# Simple_MacroPad_PCB.net
KiCad netlist of a schematic drawn in Altium Designer
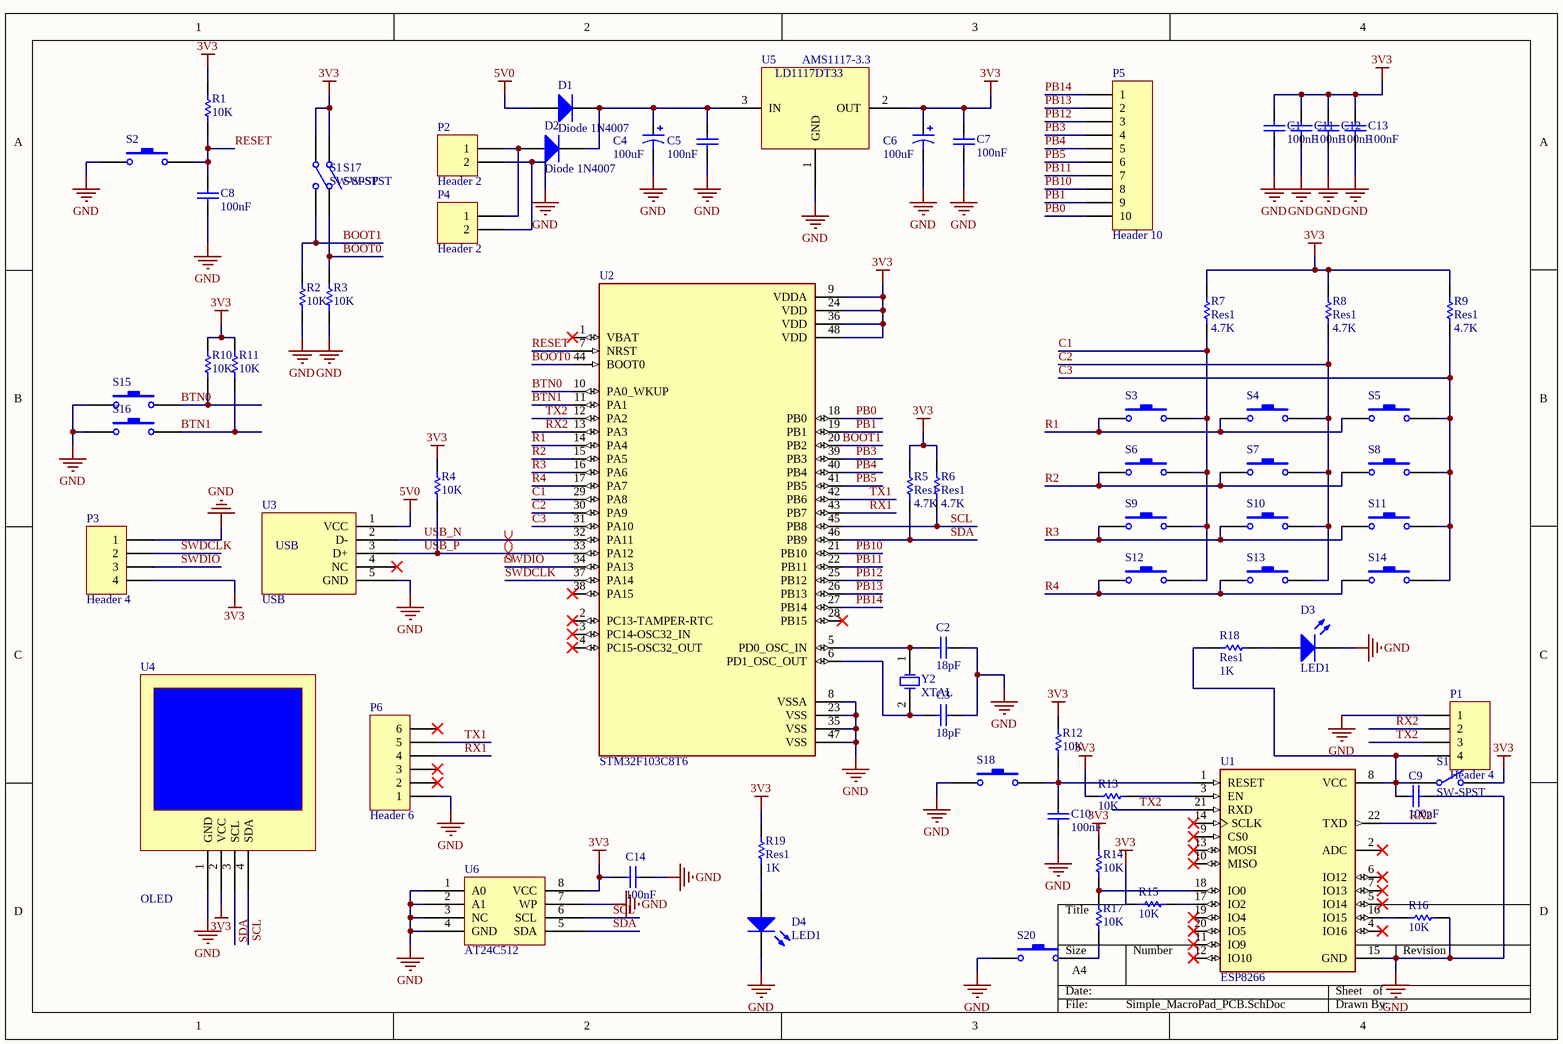
[diagram p0: Simple_MacroPad_PCB.SchDoc]

(export (version "E")
  (design (tool "Eeschema 10.0.6"))
  (components
    (comp (ref "C1")
      (value "100nF")
      (footprint "CAP_1206")
      (description "Capacitor")
      (fields (field (name "PUBLISHER") "Altium Limited"))
      (libsource (lib "Miscellaneous Devices") (part "Cap"))
    )
    (comp (ref "C2")
      (value "18pF")
      (footprint "CAP_1206")
      (description "Capacitor")
      (fields (field (name "PUBLISHER") "Altium Limited"))
      (libsource (lib "Miscellaneous Devices") (part "Cap"))
    )
    (comp (ref "C3")
      (value "18pF")
      (footprint "CAP_1206")
      (description "Capacitor")
      (fields (field (name "PUBLISHER") "Altium Limited"))
      (libsource (lib "Miscellaneous Devices") (part "Cap"))
    )
    (comp (ref "C4")
      (value "100uF")
      (footprint "CAP_TANTAL")
      (description "Polarized Capacitor (Radial)")
      (fields (field (name "PUBLISHER") "Altium Limited"))
      (libsource (lib "Miscellaneous Devices") (part "Cap Pol1"))
    )
    (comp (ref "C5")
      (value "100nF")
      (footprint "CAP_1206")
      (description "Capacitor")
      (fields (field (name "PUBLISHER") "Altium Limited"))
      (libsource (lib "Miscellaneous Devices") (part "Cap"))
    )
    (comp (ref "C6")
      (value "100uF")
      (footprint "CAP_TANTAL")
      (description "Polarized Capacitor (Radial)")
      (fields (field (name "PUBLISHER") "Altium Limited"))
      (libsource (lib "Miscellaneous Devices") (part "Cap Pol1"))
    )
    (comp (ref "C7")
      (value "100nF")
      (footprint "CAP_1206")
      (description "Capacitor")
      (fields (field (name "PUBLISHER") "Altium Limited"))
      (libsource (lib "Miscellaneous Devices") (part "Cap"))
    )
    (comp (ref "C8")
      (value "100nF")
      (footprint "CAP_1206")
      (description "Capacitor")
      (fields (field (name "PUBLISHER") "Altium Limited"))
      (libsource (lib "Miscellaneous Devices") (part "Cap"))
    )
    (comp (ref "C9")
      (value "100nF")
      (footprint "CAP_1206")
      (description "Capacitor")
      (fields (field (name "Comment") "18pF") (field (name "PUBLISHER") "Altium Limited"))
      (libsource (lib "Miscellaneous Devices") (part "Cap"))
    )
    (comp (ref "C10")
      (value "100nF")
      (footprint "CAP_1206")
      (description "Capacitor")
      (fields (field (name "Comment") "18pF") (field (name "PUBLISHER") "Altium Limited"))
      (libsource (lib "Miscellaneous Devices") (part "Cap"))
    )
    (comp (ref "C11")
      (value "100nF")
      (footprint "CAP_1206")
      (description "Capacitor")
      (fields (field (name "PUBLISHER") "Altium Limited"))
      (libsource (lib "Miscellaneous Devices") (part "Cap"))
    )
    (comp (ref "C12")
      (value "100nF")
      (footprint "CAP_1206")
      (description "Capacitor")
      (fields (field (name "PUBLISHER") "Altium Limited"))
      (libsource (lib "Miscellaneous Devices") (part "Cap"))
    )
    (comp (ref "C13")
      (value "100nF")
      (footprint "CAP_1206")
      (description "Capacitor")
      (fields (field (name "PUBLISHER") "Altium Limited"))
      (libsource (lib "Miscellaneous Devices") (part "Cap"))
    )
    (comp (ref "C14")
      (value "100nF")
      (footprint "CAP_1206")
      (description "Capacitor")
      (fields (field (name "PUBLISHER") "Altium Limited"))
      (libsource (lib "Miscellaneous Devices") (part "Cap"))
    )
    (comp (ref "D1")
      (value "Diode 1N4007")
      (footprint "DIODE")
      (description "1 Amp General Purpose Rectifier")
      (fields (field (name "PUBLISHER") "Altium Limited"))
      (libsource (lib "Miscellaneous Devices") (part "Diode 1N4007"))
    )
    (comp (ref "D2")
      (value "Diode 1N4007")
      (footprint "DIODE")
      (description "1 Amp General Purpose Rectifier")
      (fields (field (name "PUBLISHER") "Altium Limited"))
      (libsource (lib "Miscellaneous Devices") (part "Diode 1N4007"))
    )
    (comp (ref "D3")
      (value "LED1")
      (footprint "LED_1206")
      (description "Typical RED GaAs LED")
      (fields (field (name "PUBLISHER") "Altium Limited"))
      (libsource (lib "Miscellaneous Devices") (part "LED1"))
    )
    (comp (ref "D4")
      (value "LED1")
      (footprint "LED_1206")
      (description "Typical RED GaAs LED")
      (fields (field (name "PUBLISHER") "Altium Limited"))
      (libsource (lib "Miscellaneous Devices") (part "LED1"))
    )
    (comp (ref "P1")
      (value "Header 4")
      (footprint "HDR1X4")
      (description "Header, 4-Pin")
      (fields (field (name "PUBLISHER") "Altium Limited"))
      (libsource (lib "") (part "Header 4_1"))
    )
    (comp (ref "P2")
      (value "Header 2")
      (footprint "JACK")
      (description "Header, 2-Pin")
      (fields (field (name "PUBLISHER") "Altium Limited"))
      (libsource (lib "Miscellaneous Connectors") (part "Header 2"))
    )
    (comp (ref "P3")
      (value "Header 4")
      (footprint "HDR1X4")
      (description "Header, 4-Pin")
      (fields (field (name "PUBLISHER") "Altium Limited"))
      (libsource (lib "Miscellaneous Connectors") (part "Header 4"))
    )
    (comp (ref "P4")
      (value "Header 2")
      (footprint "HDR1X2")
      (description "Header, 2-Pin")
      (fields (field (name "PUBLISHER") "Altium Limited"))
      (libsource (lib "Miscellaneous Connectors") (part "Header 2"))
    )
    (comp (ref "P5")
      (value "Header 10")
      (footprint "HEADER10")
      (description "Header, 10-Pin")
      (fields (field (name "PUBLISHER") "Altium Limited"))
      (libsource (lib "Miscellaneous Connectors") (part "Header 10"))
    )
    (comp (ref "P6")
      (value "Header 6")
      (footprint "HEADER6")
      (description "Header, 6-Pin")
      (fields (field (name "PUBLISHER") "Altium Limited"))
      (libsource (lib "Miscellaneous Connectors") (part "Header 6"))
    )
    (comp (ref "R1")
      (value "10K")
      (footprint "RES_1206")
      (description "Resistor")
      (fields (field (name "PUBLISHER") "Altium Limited"))
      (libsource (lib "Miscellaneous Devices") (part "Res1"))
    )
    (comp (ref "R2")
      (value "10K")
      (footprint "RES_1206")
      (description "Resistor")
      (fields (field (name "PUBLISHER") "Altium Limited"))
      (libsource (lib "Miscellaneous Devices") (part "Res1"))
    )
    (comp (ref "R3")
      (value "10K")
      (footprint "RES_1206")
      (description "Resistor")
      (fields (field (name "PUBLISHER") "Altium Limited"))
      (libsource (lib "Miscellaneous Devices") (part "Res1"))
    )
    (comp (ref "R4")
      (value "10K")
      (footprint "RES_1206")
      (description "Resistor")
      (fields (field (name "Comment") "1.5K") (field (name "PUBLISHER") "Altium Limited"))
      (libsource (lib "Miscellaneous Devices") (part "Res1"))
    )
    (comp (ref "R5")
      (value "Res1")
      (footprint "RES_1206")
      (description "Resistor")
      (fields (field (name "ALTIUM_VALUE") "4.7K") (field (name "PUBLISHER") "Altium Limited"))
      (libsource (lib "Miscellaneous Devices") (part "Res1"))
    )
    (comp (ref "R6")
      (value "Res1")
      (footprint "RES_1206")
      (description "Resistor")
      (fields (field (name "ALTIUM_VALUE") "4.7K") (field (name "PUBLISHER") "Altium Limited"))
      (libsource (lib "Miscellaneous Devices") (part "Res1"))
    )
    (comp (ref "R7")
      (value "Res1")
      (footprint "RES_1206")
      (description "Resistor")
      (fields (field (name "ALTIUM_VALUE") "4.7K") (field (name "PUBLISHER") "Altium Limited"))
      (libsource (lib "Miscellaneous Devices") (part "Res1"))
    )
    (comp (ref "R8")
      (value "Res1")
      (footprint "RES_1206")
      (description "Resistor")
      (fields (field (name "ALTIUM_VALUE") "4.7K") (field (name "PUBLISHER") "Altium Limited"))
      (libsource (lib "Miscellaneous Devices") (part "Res1"))
    )
    (comp (ref "R9")
      (value "Res1")
      (footprint "RES_1206")
      (description "Resistor")
      (fields (field (name "ALTIUM_VALUE") "4.7K") (field (name "PUBLISHER") "Altium Limited"))
      (libsource (lib "Miscellaneous Devices") (part "Res1"))
    )
    (comp (ref "R10")
      (value "10K")
      (footprint "RES_1206")
      (description "Resistor")
      (fields (field (name "PUBLISHER") "Altium Limited"))
      (libsource (lib "Miscellaneous Devices") (part "Res1"))
    )
    (comp (ref "R11")
      (value "10K")
      (footprint "RES_1206")
      (description "Resistor")
      (fields (field (name "PUBLISHER") "Altium Limited"))
      (libsource (lib "Miscellaneous Devices") (part "Res1"))
    )
    (comp (ref "R12")
      (value "10K")
      (footprint "RES_1206")
      (description "Resistor")
      (fields (field (name "PUBLISHER") "Altium Limited"))
      (libsource (lib "Miscellaneous Devices") (part "Res1"))
    )
    (comp (ref "R13")
      (value "10K")
      (footprint "RES_1206")
      (description "Resistor")
      (fields (field (name "PUBLISHER") "Altium Limited"))
      (libsource (lib "Miscellaneous Devices") (part "Res1"))
    )
    (comp (ref "R14")
      (value "10K")
      (footprint "RES_1206")
      (description "Resistor")
      (fields (field (name "PUBLISHER") "Altium Limited"))
      (libsource (lib "Miscellaneous Devices") (part "Res1"))
    )
    (comp (ref "R15")
      (value "10K")
      (footprint "RES_1206")
      (description "Resistor")
      (fields (field (name "PUBLISHER") "Altium Limited"))
      (libsource (lib "Miscellaneous Devices") (part "Res1"))
    )
    (comp (ref "R16")
      (value "10K")
      (footprint "RES_1206")
      (description "Resistor")
      (fields (field (name "PUBLISHER") "Altium Limited"))
      (libsource (lib "Miscellaneous Devices") (part "Res1"))
    )
    (comp (ref "R17")
      (value "10K")
      (footprint "RES_1206")
      (description "Resistor")
      (fields (field (name "PUBLISHER") "Altium Limited"))
      (libsource (lib "Miscellaneous Devices") (part "Res1"))
    )
    (comp (ref "R18")
      (value "Res1")
      (footprint "RES_1206")
      (description "Resistor")
      (fields (field (name "ALTIUM_VALUE") "1K") (field (name "PUBLISHER") "Altium Limited"))
      (libsource (lib "Miscellaneous Devices") (part "Res1"))
    )
    (comp (ref "R19")
      (value "Res1")
      (footprint "RES_1206")
      (description "Resistor")
      (fields (field (name "ALTIUM_VALUE") "1K") (field (name "PUBLISHER") "Altium Limited"))
      (libsource (lib "Miscellaneous Devices") (part "Res1"))
    )
    (comp (ref "S1")
      (value "SW-SPST")
      (footprint "SW_DIP1")
      (description "Single-Pole, Single-Throw Switch")
      (fields (field (name "PUBLISHER") "Altium Limited"))
      (libsource (lib "Miscellaneous Devices") (part "SW-SPST"))
    )
    (comp (ref "S2")
      (value "PB")
      (footprint "BUTTON")
      (description "Switch")
      (fields (field (name "PUBLISHER") "Altium Limited"))
      (libsource (lib "Miscellaneous Devices") (part "SW-PB"))
    )
    (comp (ref "S3")
      (value "PB")
      (footprint "BUTTON")
      (description "Switch")
      (fields (field (name "PUBLISHER") "Altium Limited"))
      (libsource (lib "Miscellaneous Devices") (part "SW-PB"))
    )
    (comp (ref "S4")
      (value "PB")
      (footprint "BUTTON")
      (description "Switch")
      (fields (field (name "PUBLISHER") "Altium Limited"))
      (libsource (lib "Miscellaneous Devices") (part "SW-PB"))
    )
    (comp (ref "S5")
      (value "PB")
      (footprint "BUTTON")
      (description "Switch")
      (fields (field (name "PUBLISHER") "Altium Limited"))
      (libsource (lib "Miscellaneous Devices") (part "SW-PB"))
    )
    (comp (ref "S6")
      (value "PB")
      (footprint "BUTTON")
      (description "Switch")
      (fields (field (name "PUBLISHER") "Altium Limited"))
      (libsource (lib "Miscellaneous Devices") (part "SW-PB"))
    )
    (comp (ref "S7")
      (value "PB")
      (footprint "BUTTON")
      (description "Switch")
      (fields (field (name "PUBLISHER") "Altium Limited"))
      (libsource (lib "Miscellaneous Devices") (part "SW-PB"))
    )
    (comp (ref "S8")
      (value "PB")
      (footprint "BUTTON")
      (description "Switch")
      (fields (field (name "PUBLISHER") "Altium Limited"))
      (libsource (lib "Miscellaneous Devices") (part "SW-PB"))
    )
    (comp (ref "S9")
      (value "PB")
      (footprint "BUTTON")
      (description "Switch")
      (fields (field (name "PUBLISHER") "Altium Limited"))
      (libsource (lib "Miscellaneous Devices") (part "SW-PB"))
    )
    (comp (ref "S10")
      (value "PB")
      (footprint "BUTTON")
      (description "Switch")
      (fields (field (name "PUBLISHER") "Altium Limited"))
      (libsource (lib "Miscellaneous Devices") (part "SW-PB"))
    )
    (comp (ref "S11")
      (value "PB")
      (footprint "BUTTON")
      (description "Switch")
      (fields (field (name "PUBLISHER") "Altium Limited"))
      (libsource (lib "Miscellaneous Devices") (part "SW-PB"))
    )
    (comp (ref "S12")
      (value "PB")
      (footprint "BUTTON")
      (description "Switch")
      (fields (field (name "PUBLISHER") "Altium Limited"))
      (libsource (lib "Miscellaneous Devices") (part "SW-PB"))
    )
    (comp (ref "S13")
      (value "PB")
      (footprint "BUTTON")
      (description "Switch")
      (fields (field (name "PUBLISHER") "Altium Limited"))
      (libsource (lib "Miscellaneous Devices") (part "SW-PB"))
    )
    (comp (ref "S14")
      (value "PB")
      (footprint "BUTTON")
      (description "Switch")
      (fields (field (name "PUBLISHER") "Altium Limited"))
      (libsource (lib "Miscellaneous Devices") (part "SW-PB"))
    )
    (comp (ref "S15")
      (value "PB")
      (footprint "BUTTON")
      (description "Switch")
      (fields (field (name "PUBLISHER") "Altium Limited"))
      (libsource (lib "Miscellaneous Devices") (part "SW-PB"))
    )
    (comp (ref "S16")
      (value "PB")
      (footprint "BUTTON")
      (description "Switch")
      (fields (field (name "PUBLISHER") "Altium Limited"))
      (libsource (lib "Miscellaneous Devices") (part "SW-PB"))
    )
    (comp (ref "S17")
      (value "SW-SPST")
      (footprint "SW_DIP1")
      (description "Single-Pole, Single-Throw Switch")
      (fields (field (name "PUBLISHER") "Altium Limited"))
      (libsource (lib "Miscellaneous Devices") (part "SW-SPST"))
    )
    (comp (ref "S18")
      (value "PB")
      (footprint "BUTTON")
      (description "Switch")
      (fields (field (name "PUBLISHER") "Altium Limited"))
      (libsource (lib "Miscellaneous Devices") (part "SW-PB"))
    )
    (comp (ref "S19")
      (value "SW-SPST")
      (footprint "SW_DIP1")
      (description "Single-Pole, Single-Throw Switch")
      (fields (field (name "PUBLISHER") "Altium Limited"))
      (libsource (lib "Miscellaneous Devices") (part "SW-SPST"))
    )
    (comp (ref "S20")
      (value "PB")
      (footprint "BUTTON")
      (description "Switch")
      (fields (field (name "PUBLISHER") "Altium Limited"))
      (libsource (lib "Miscellaneous Devices") (part "SW-PB"))
    )
    (comp (ref "U1")
      (value "ESP8266")
      (footprint "PCBComponent_1")
      (libsource (lib "ESP8266") (part "ESP8266"))
    )
    (comp (ref "U2")
      (value "STM32F103C8T6")
      (footprint "STM32f103C8T6")
      (libsource (lib "STM32F103C8T6") (part "STM32F103C8T6"))
    )
    (comp (ref "U3") (value "USB") (footprint "MICRO_USB") (libsource (lib "USB") (part "USB")))
    (comp (ref "U4") (value "OLED") (footprint "OLED") (libsource (lib "OLED") (part "OLED")))
    (comp (ref "U5")
      (value "AMS1117-3.3")
      (footprint "AMS1117")
      (libsource (lib "LD1117DT33") (part "LD1117DT33"))
    )
    (comp (ref "U6") (value "AT24C512") (footprint "AT24C512") (libsource (lib "AT24C512") (part "AT24C512")))
    (comp (ref "Y2")
      (value "XTAL")
      (footprint "CRYSTAL")
      (description "Crystal Oscillator")
      (fields (field (name "PUBLISHER") "Altium Limited"))
      (libsource (lib "Miscellaneous Devices") (part "XTAL"))
    )
  )
  (nets
    (net (code "1") (name "/BOOT0") (class "Default")
      (node (ref "R3") (pin "2") (pinfunction "2_2") (pintype "passive"))
      (node (ref "S17") (pin "2") (pinfunction "NO_2") (pintype "passive"))
      (node (ref "U2") (pin "44") (pinfunction "BOOT0_44") (pintype "input"))
    )
    (net (code "2") (name "/BOOT1") (class "Default")
      (node (ref "R2") (pin "2") (pinfunction "2_2") (pintype "passive"))
      (node (ref "S1") (pin "2") (pinfunction "NO_2") (pintype "passive"))
      (node (ref "U2") (pin "20") (pinfunction "PB2_20") (pintype "bidirectional"))
    )
    (net (code "3") (name "/BTN0") (class "Default")
      (node (ref "R10") (pin "1") (pinfunction "1_1") (pintype "passive"))
      (node (ref "S15") (pin "2") (pinfunction "2_2") (pintype "passive"))
      (node (ref "U2") (pin "10") (pinfunction "PA0_WKUP_10") (pintype "bidirectional"))
    )
    (net (code "4") (name "/BTN1") (class "Default")
      (node (ref "R11") (pin "1") (pinfunction "1_1") (pintype "passive"))
      (node (ref "S16") (pin "2") (pinfunction "2_2") (pintype "passive"))
      (node (ref "U2") (pin "11") (pinfunction "PA1_11") (pintype "bidirectional"))
    )
    (net (code "5") (name "/C1") (class "Default")
      (node (ref "R7") (pin "1") (pinfunction "1_1") (pintype "passive"))
      (node (ref "S12") (pin "2") (pinfunction "2_2") (pintype "passive"))
      (node (ref "S3") (pin "2") (pinfunction "2_2") (pintype "passive"))
      (node (ref "S6") (pin "2") (pinfunction "2_2") (pintype "passive"))
      (node (ref "S9") (pin "2") (pinfunction "2_2") (pintype "passive"))
      (node (ref "U2") (pin "29") (pinfunction "PA8_29") (pintype "bidirectional"))
    )
    (net (code "6") (name "/C2") (class "Default")
      (node (ref "R8") (pin "1") (pinfunction "1_1") (pintype "passive"))
      (node (ref "S10") (pin "2") (pinfunction "2_2") (pintype "passive"))
      (node (ref "S13") (pin "2") (pinfunction "2_2") (pintype "passive"))
      (node (ref "S4") (pin "2") (pinfunction "2_2") (pintype "passive"))
      (node (ref "S7") (pin "2") (pinfunction "2_2") (pintype "passive"))
      (node (ref "U2") (pin "30") (pinfunction "PA9_30") (pintype "bidirectional"))
    )
    (net (code "7") (name "/C3") (class "Default")
      (node (ref "R9") (pin "1") (pinfunction "1_1") (pintype "passive"))
      (node (ref "S11") (pin "2") (pinfunction "2_2") (pintype "passive"))
      (node (ref "S14") (pin "2") (pinfunction "2_2") (pintype "passive"))
      (node (ref "S5") (pin "2") (pinfunction "2_2") (pintype "passive"))
      (node (ref "S8") (pin "2") (pinfunction "2_2") (pintype "passive"))
      (node (ref "U2") (pin "31") (pinfunction "PA10_31") (pintype "bidirectional"))
    )
    (net (code "8") (name "/PB0") (class "Default")
      (node (ref "P5") (pin "10") (pinfunction "10_10") (pintype "passive"))
      (node (ref "U2") (pin "18") (pinfunction "PB0_18") (pintype "bidirectional"))
    )
    (net (code "9") (name "/PB1") (class "Default")
      (node (ref "P5") (pin "9") (pinfunction "9_9") (pintype "passive"))
      (node (ref "U2") (pin "19") (pinfunction "PB1_19") (pintype "bidirectional"))
    )
    (net (code "10") (name "/PB3") (class "Default")
      (node (ref "P5") (pin "4") (pinfunction "4_4") (pintype "passive"))
      (node (ref "U2") (pin "39") (pinfunction "PB3_39") (pintype "bidirectional"))
    )
    (net (code "11") (name "/PB4") (class "Default")
      (node (ref "P5") (pin "5") (pinfunction "5_5") (pintype "passive"))
      (node (ref "U2") (pin "40") (pinfunction "PB4_40") (pintype "bidirectional"))
    )
    (net (code "12") (name "/PB5") (class "Default")
      (node (ref "P5") (pin "6") (pinfunction "6_6") (pintype "passive"))
      (node (ref "U2") (pin "41") (pinfunction "PB5_41") (pintype "bidirectional"))
    )
    (net (code "13") (name "/PB10") (class "Default")
      (node (ref "P5") (pin "8") (pinfunction "8_8") (pintype "passive"))
      (node (ref "U2") (pin "21") (pinfunction "PB10_21") (pintype "bidirectional"))
    )
    (net (code "14") (name "/PB11") (class "Default")
      (node (ref "P5") (pin "7") (pinfunction "7_7") (pintype "passive"))
      (node (ref "U2") (pin "22") (pinfunction "PB11_22") (pintype "bidirectional"))
    )
    (net (code "15") (name "/PB12") (class "Default")
      (node (ref "P5") (pin "3") (pinfunction "3_3") (pintype "passive"))
      (node (ref "U2") (pin "25") (pinfunction "PB12_25") (pintype "bidirectional"))
    )
    (net (code "16") (name "/PB13") (class "Default")
      (node (ref "P5") (pin "2") (pinfunction "2_2") (pintype "passive"))
      (node (ref "U2") (pin "26") (pinfunction "PB13_26") (pintype "bidirectional"))
    )
    (net (code "17") (name "/PB14") (class "Default")
      (node (ref "P5") (pin "1") (pinfunction "1_1") (pintype "passive"))
      (node (ref "U2") (pin "27") (pinfunction "PB14_27") (pintype "bidirectional"))
    )
    (net (code "18") (name "/R1") (class "Default")
      (node (ref "S3") (pin "1") (pinfunction "1_1") (pintype "passive"))
      (node (ref "S4") (pin "1") (pinfunction "1_1") (pintype "passive"))
      (node (ref "S5") (pin "1") (pinfunction "1_1") (pintype "passive"))
      (node (ref "U2") (pin "14") (pinfunction "PA4_14") (pintype "bidirectional"))
    )
    (net (code "19") (name "/R2") (class "Default")
      (node (ref "S6") (pin "1") (pinfunction "1_1") (pintype "passive"))
      (node (ref "S7") (pin "1") (pinfunction "1_1") (pintype "passive"))
      (node (ref "S8") (pin "1") (pinfunction "1_1") (pintype "passive"))
      (node (ref "U2") (pin "15") (pinfunction "PA5_15") (pintype "bidirectional"))
    )
    (net (code "20") (name "/R3") (class "Default")
      (node (ref "S10") (pin "1") (pinfunction "1_1") (pintype "passive"))
      (node (ref "S11") (pin "1") (pinfunction "1_1") (pintype "passive"))
      (node (ref "S9") (pin "1") (pinfunction "1_1") (pintype "passive"))
      (node (ref "U2") (pin "16") (pinfunction "PA6_16") (pintype "bidirectional"))
    )
    (net (code "21") (name "/R4") (class "Default")
      (node (ref "S12") (pin "1") (pinfunction "1_1") (pintype "passive"))
      (node (ref "S13") (pin "1") (pinfunction "1_1") (pintype "passive"))
      (node (ref "S14") (pin "1") (pinfunction "1_1") (pintype "passive"))
      (node (ref "U2") (pin "17") (pinfunction "PA7_17") (pintype "bidirectional"))
    )
    (net (code "22") (name "/RESET") (class "Default")
      (node (ref "C8") (pin "2") (pinfunction "2_2") (pintype "passive"))
      (node (ref "R1") (pin "1") (pinfunction "1_1") (pintype "passive"))
      (node (ref "S2") (pin "2") (pinfunction "2_2") (pintype "passive"))
      (node (ref "U2") (pin "7") (pinfunction "NRST_7") (pintype "input"))
    )
    (net (code "23") (name "/RX1") (class "Default")
      (node (ref "P6") (pin "4") (pinfunction "4_4") (pintype "passive"))
      (node (ref "U2") (pin "43") (pinfunction "PB7_43") (pintype "bidirectional"))
    )
    (net (code "24") (name "/RX2") (class "Default")
      (node (ref "P1") (pin "2") (pinfunction "2_2") (pintype "passive"))
      (node (ref "U1") (pin "22") (pinfunction "TXD_22") (pintype "output"))
      (node (ref "U2") (pin "13") (pinfunction "PA3_13") (pintype "bidirectional"))
    )
    (net (code "25") (name "/SCL") (class "Default")
      (node (ref "R6") (pin "1") (pinfunction "1_1") (pintype "passive"))
      (node (ref "U2") (pin "45") (pinfunction "PB8_45") (pintype "bidirectional"))
      (node (ref "U4") (pin "4") (pinfunction "SDA_4") (pintype "passive"))
      (node (ref "U6") (pin "6") (pinfunction "SCL_6") (pintype "passive"))
    )
    (net (code "26") (name "/SDA") (class "Default")
      (node (ref "R5") (pin "1") (pinfunction "1_1") (pintype "passive"))
      (node (ref "U2") (pin "46") (pinfunction "PB9_46") (pintype "bidirectional"))
      (node (ref "U4") (pin "3") (pinfunction "SCL_3") (pintype "passive"))
      (node (ref "U6") (pin "5") (pinfunction "SDA_5") (pintype "passive"))
    )
    (net (code "27") (name "/SWDCLK") (class "Default")
      (node (ref "P3") (pin "2") (pinfunction "2_2") (pintype "passive"))
      (node (ref "U2") (pin "37") (pinfunction "PA14_37") (pintype "bidirectional"))
    )
    (net (code "28") (name "/SWDIO") (class "Default")
      (node (ref "P3") (pin "3") (pinfunction "3_3") (pintype "passive"))
      (node (ref "U2") (pin "34") (pinfunction "PA13_34") (pintype "bidirectional"))
    )
    (net (code "29") (name "/TX1") (class "Default")
      (node (ref "P6") (pin "5") (pinfunction "5_5") (pintype "passive"))
      (node (ref "U2") (pin "42") (pinfunction "PB6_42") (pintype "bidirectional"))
    )
    (net (code "30") (name "/TX2") (class "Default")
      (node (ref "P1") (pin "3") (pinfunction "3_3") (pintype "passive"))
      (node (ref "U1") (pin "21") (pinfunction "RXD_21") (pintype "input"))
      (node (ref "U2") (pin "12") (pinfunction "PA2_12") (pintype "bidirectional"))
    )
    (net (code "31") (name "/USB_N") (class "Default")
      (node (ref "U2") (pin "32") (pinfunction "PA11_32") (pintype "bidirectional"))
      (node (ref "U3") (pin "2") (pinfunction "D-_2") (pintype "passive"))
    )
    (net (code "32") (name "/USB_P") (class "Default")
      (node (ref "R4") (pin "1") (pinfunction "1_1") (pintype "passive"))
      (node (ref "U2") (pin "33") (pinfunction "PA12_33") (pintype "bidirectional"))
      (node (ref "U3") (pin "3") (pinfunction "D+_3") (pintype "passive"))
    )
    (net (code "33") (name "3V3") (class "Default")
      (node (ref "C1") (pin "2") (pinfunction "2_2") (pintype "passive"))
      (node (ref "C11") (pin "2") (pinfunction "2_2") (pintype "passive"))
      (node (ref "C12") (pin "2") (pinfunction "2_2") (pintype "passive"))
      (node (ref "C13") (pin "2") (pinfunction "2_2") (pintype "passive"))
      (node (ref "C14") (pin "2") (pinfunction "2_2") (pintype "passive"))
      (node (ref "C6") (pin "1") (pinfunction "1_1") (pintype "passive"))
      (node (ref "C7") (pin "2") (pinfunction "2_2") (pintype "passive"))
      (node (ref "P3") (pin "4") (pinfunction "4_4") (pintype "passive"))
      (node (ref "R1") (pin "2") (pinfunction "2_2") (pintype "passive"))
      (node (ref "R10") (pin "2") (pinfunction "2_2") (pintype "passive"))
      (node (ref "R11") (pin "2") (pinfunction "2_2") (pintype "passive"))
      (node (ref "R12") (pin "2") (pinfunction "2_2") (pintype "passive"))
      (node (ref "R13") (pin "2") (pinfunction "2_2") (pintype "passive"))
      (node (ref "R14") (pin "2") (pinfunction "2_2") (pintype "passive"))
      (node (ref "R15") (pin "2") (pinfunction "2_2") (pintype "passive"))
      (node (ref "R19") (pin "2") (pinfunction "2_2") (pintype "passive"))
      (node (ref "R4") (pin "2") (pinfunction "2_2") (pintype "passive"))
      (node (ref "R5") (pin "2") (pinfunction "2_2") (pintype "passive"))
      (node (ref "R6") (pin "2") (pinfunction "2_2") (pintype "passive"))
      (node (ref "R7") (pin "2") (pinfunction "2_2") (pintype "passive"))
      (node (ref "R8") (pin "2") (pinfunction "2_2") (pintype "passive"))
      (node (ref "R9") (pin "2") (pinfunction "2_2") (pintype "passive"))
      (node (ref "S1") (pin "1") (pinfunction "COMMON_1") (pintype "passive"))
      (node (ref "S17") (pin "1") (pinfunction "COMMON_1") (pintype "passive"))
      (node (ref "S19") (pin "2") (pinfunction "NO_2") (pintype "passive"))
      (node (ref "U2") (pin "24") (pinfunction "VDD_24") (pintype "power_in"))
      (node (ref "U2") (pin "36") (pinfunction "VDD_36") (pintype "power_in"))
      (node (ref "U2") (pin "48") (pinfunction "VDD_48") (pintype "power_in"))
      (node (ref "U2") (pin "9") (pinfunction "VDDA_9") (pintype "power_in"))
      (node (ref "U4") (pin "2") (pinfunction "VCC_2") (pintype "passive"))
      (node (ref "U5") (pin "2") (pinfunction "OUT_2") (pintype "passive"))
      (node (ref "U6") (pin "8") (pinfunction "VCC_8") (pintype "passive"))
    )
    (net (code "34") (name "5V0") (class "Default")
      (node (ref "D1") (pin "1") (pinfunction "A_1") (pintype "passive"))
      (node (ref "U3") (pin "1") (pinfunction "VCC_1") (pintype "passive"))
    )
    (net (code "35") (name "GND") (class "Default")
      (node (ref "C1") (pin "1") (pinfunction "1_1") (pintype "passive"))
      (node (ref "C10") (pin "2") (pinfunction "2_2") (pintype "passive"))
      (node (ref "C11") (pin "1") (pinfunction "1_1") (pintype "passive"))
      (node (ref "C12") (pin "1") (pinfunction "1_1") (pintype "passive"))
      (node (ref "C13") (pin "1") (pinfunction "1_1") (pintype "passive"))
      (node (ref "C14") (pin "1") (pinfunction "1_1") (pintype "passive"))
      (node (ref "C2") (pin "1") (pinfunction "1_1") (pintype "passive"))
      (node (ref "C3") (pin "1") (pinfunction "1_1") (pintype "passive"))
      (node (ref "C4") (pin "2") (pinfunction "2_2") (pintype "passive"))
      (node (ref "C5") (pin "1") (pinfunction "1_1") (pintype "passive"))
      (node (ref "C6") (pin "2") (pinfunction "2_2") (pintype "passive"))
      (node (ref "C7") (pin "1") (pinfunction "1_1") (pintype "passive"))
      (node (ref "C8") (pin "1") (pinfunction "1_1") (pintype "passive"))
      (node (ref "C9") (pin "2") (pinfunction "2_2") (pintype "passive"))
      (node (ref "D3") (pin "2") (pinfunction "K_2") (pintype "passive"))
      (node (ref "D4") (pin "2") (pinfunction "K_2") (pintype "passive"))
      (node (ref "P1") (pin "1") (pinfunction "1_1") (pintype "passive"))
      (node (ref "P2") (pin "2") (pinfunction "2_2") (pintype "passive"))
      (node (ref "P3") (pin "1") (pinfunction "1_1") (pintype "passive"))
      (node (ref "P4") (pin "2") (pinfunction "2_2") (pintype "passive"))
      (node (ref "P6") (pin "1") (pinfunction "1_1") (pintype "passive"))
      (node (ref "R16") (pin "1") (pinfunction "1_1") (pintype "passive"))
      (node (ref "R2") (pin "1") (pinfunction "1_1") (pintype "passive"))
      (node (ref "R3") (pin "1") (pinfunction "1_1") (pintype "passive"))
      (node (ref "S15") (pin "1") (pinfunction "1_1") (pintype "passive"))
      (node (ref "S16") (pin "1") (pinfunction "1_1") (pintype "passive"))
      (node (ref "S18") (pin "1") (pinfunction "1_1") (pintype "passive"))
      (node (ref "S2") (pin "1") (pinfunction "1_1") (pintype "passive"))
      (node (ref "S20") (pin "1") (pinfunction "1_1") (pintype "passive"))
      (node (ref "U1") (pin "15") (pinfunction "GND_15") (pintype "power_in"))
      (node (ref "U2") (pin "23") (pinfunction "VSS_23") (pintype "power_in"))
      (node (ref "U2") (pin "35") (pinfunction "VSS_35") (pintype "power_in"))
      (node (ref "U2") (pin "47") (pinfunction "VSS_47") (pintype "power_in"))
      (node (ref "U2") (pin "8") (pinfunction "VSSA_8") (pintype "power_in"))
      (node (ref "U3") (pin "5") (pinfunction "GND_5") (pintype "passive"))
      (node (ref "U4") (pin "1") (pinfunction "GND_1") (pintype "passive"))
      (node (ref "U5") (pin "1") (pinfunction "GND_1") (pintype "passive"))
      (node (ref "U6") (pin "1") (pinfunction "A0_1") (pintype "passive"))
      (node (ref "U6") (pin "2") (pinfunction "A1_2") (pintype "passive"))
      (node (ref "U6") (pin "3") (pinfunction "NC_3") (pintype "passive"))
      (node (ref "U6") (pin "4") (pinfunction "GND_4") (pintype "passive"))
      (node (ref "U6") (pin "7") (pinfunction "WP_7") (pintype "passive"))
    )
    (net (code "36") (name "Net-(D1-K)") (class "Default")
      (node (ref "C4") (pin "1") (pinfunction "1_1") (pintype "passive"))
      (node (ref "C5") (pin "2") (pinfunction "2_2") (pintype "passive"))
      (node (ref "D1") (pin "2") (pinfunction "K_2") (pintype "passive"))
      (node (ref "D2") (pin "2") (pinfunction "K_2") (pintype "passive"))
      (node (ref "U5") (pin "3") (pinfunction "IN_3") (pintype "passive"))
    )
    (net (code "37") (name "Net-(D2-A)") (class "Default")
      (node (ref "D2") (pin "1") (pinfunction "A_1") (pintype "passive"))
      (node (ref "P2") (pin "1") (pinfunction "1_1") (pintype "passive"))
      (node (ref "P4") (pin "1") (pinfunction "1_1") (pintype "passive"))
    )
    (net (code "38") (name "Net-(D3-A)") (class "Default")
      (node (ref "D3") (pin "1") (pinfunction "A_1") (pintype "passive"))
      (node (ref "R18") (pin "1") (pinfunction "1_1") (pintype "passive"))
    )
    (net (code "39") (name "Net-(D4-A)") (class "Default")
      (node (ref "D4") (pin "1") (pinfunction "A_1") (pintype "passive"))
      (node (ref "R19") (pin "1") (pinfunction "1_1") (pintype "passive"))
    )
    (net (code "40") (name "Net-(R17-Pad1)") (class "Default")
      (node (ref "R17") (pin "1") (pinfunction "1_1") (pintype "passive"))
      (node (ref "S20") (pin "2") (pinfunction "2_2") (pintype "passive"))
    )
    (net (code "41") (name "Net-(S19-COMMON)") (class "Default")
      (node (ref "C9") (pin "1") (pinfunction "1_1") (pintype "passive"))
      (node (ref "P1") (pin "4") (pinfunction "4_4") (pintype "passive"))
      (node (ref "R18") (pin "2") (pinfunction "2_2") (pintype "passive"))
      (node (ref "S19") (pin "1") (pinfunction "COMMON_1") (pintype "passive"))
      (node (ref "U1") (pin "8") (pinfunction "VCC_8") (pintype "power_in"))
    )
    (net (code "42") (name "Net-(U1-EN)") (class "Default")
      (node (ref "R13") (pin "1") (pinfunction "1_1") (pintype "passive"))
      (node (ref "U1") (pin "3") (pinfunction "EN_3") (pintype "input"))
    )
    (net (code "43") (name "Net-(U1-IO0)") (class "Default")
      (node (ref "R14") (pin "1") (pinfunction "1_1") (pintype "passive"))
      (node (ref "R17") (pin "2") (pinfunction "2_2") (pintype "passive"))
      (node (ref "U1") (pin "18") (pinfunction "IO0_18") (pintype "bidirectional"))
    )
    (net (code "44") (name "Net-(U1-IO2)") (class "Default")
      (node (ref "R15") (pin "1") (pinfunction "1_1") (pintype "passive"))
      (node (ref "U1") (pin "17") (pinfunction "IO2_17") (pintype "bidirectional"))
    )
    (net (code "45") (name "Net-(U1-IO15)") (class "Default")
      (node (ref "R16") (pin "2") (pinfunction "2_2") (pintype "passive"))
      (node (ref "U1") (pin "16") (pinfunction "IO15_16") (pintype "bidirectional"))
    )
    (net (code "46") (name "Net-(U1-RESET)") (class "Default")
      (node (ref "C10") (pin "1") (pinfunction "1_1") (pintype "passive"))
      (node (ref "R12") (pin "1") (pinfunction "1_1") (pintype "passive"))
      (node (ref "S18") (pin "2") (pinfunction "2_2") (pintype "passive"))
      (node (ref "U1") (pin "1") (pinfunction "RESET_1") (pintype "input"))
    )
    (net (code "47") (name "Net-(U2-PD0_OSC_IN)") (class "Default")
      (node (ref "C2") (pin "2") (pinfunction "2_2") (pintype "passive"))
      (node (ref "U2") (pin "5") (pinfunction "PD0_OSC_IN_5") (pintype "bidirectional"))
      (node (ref "Y2") (pin "1") (pinfunction "OSC1_1") (pintype "passive"))
    )
    (net (code "48") (name "Net-(U2-PD1_OSC_OUT)") (class "Default")
      (node (ref "C3") (pin "2") (pinfunction "2_2") (pintype "passive"))
      (node (ref "U2") (pin "6") (pinfunction "PD1_OSC_OUT_6") (pintype "bidirectional"))
      (node (ref "Y2") (pin "2") (pinfunction "OSC2_2") (pintype "passive"))
    )
    (net (code "49") (name "unconnected-(P6-Pad2)") (class "Default")
      (node (ref "P6") (pin "2") (pinfunction "2_2") (pintype "passive+no_connect"))
    )
    (net (code "50") (name "unconnected-(P6-Pad3)") (class "Default")
      (node (ref "P6") (pin "3") (pinfunction "3_3") (pintype "passive+no_connect"))
    )
    (net (code "51") (name "unconnected-(P6-Pad6)") (class "Default")
      (node (ref "P6") (pin "6") (pinfunction "6_6") (pintype "passive+no_connect"))
    )
    (net (code "52") (name "unconnected-(U1-ADC-Pad2)") (class "Default")
      (node (ref "U1") (pin "2") (pinfunction "ADC_2") (pintype "passive+no_connect"))
    )
    (net (code "53") (name "unconnected-(U1-CS0-Pad9)") (class "Default")
      (node (ref "U1") (pin "9") (pinfunction "CS0_9") (pintype "input+no_connect"))
    )
    (net (code "54") (name "unconnected-(U1-IO4-Pad19)") (class "Default")
      (node (ref "U1") (pin "19") (pinfunction "IO4_19") (pintype "bidirectional+no_connect"))
    )
    (net (code "55") (name "unconnected-(U1-IO5-Pad20)") (class "Default")
      (node (ref "U1") (pin "20") (pinfunction "IO5_20") (pintype "bidirectional+no_connect"))
    )
    (net (code "56") (name "unconnected-(U1-IO9-Pad11)") (class "Default")
      (node (ref "U1") (pin "11") (pinfunction "IO9_11") (pintype "bidirectional+no_connect"))
    )
    (net (code "57") (name "unconnected-(U1-IO10-Pad12)") (class "Default")
      (node (ref "U1") (pin "12") (pinfunction "IO10_12") (pintype "bidirectional+no_connect"))
    )
    (net (code "58") (name "unconnected-(U1-IO12-Pad6)") (class "Default")
      (node (ref "U1") (pin "6") (pinfunction "IO12_6") (pintype "bidirectional+no_connect"))
    )
    (net (code "59") (name "unconnected-(U1-IO13-Pad7)") (class "Default")
      (node (ref "U1") (pin "7") (pinfunction "IO13_7") (pintype "bidirectional+no_connect"))
    )
    (net (code "60") (name "unconnected-(U1-IO14-Pad5)") (class "Default")
      (node (ref "U1") (pin "5") (pinfunction "IO14_5") (pintype "bidirectional+no_connect"))
    )
    (net (code "61") (name "unconnected-(U1-IO16-Pad4)") (class "Default")
      (node (ref "U1") (pin "4") (pinfunction "IO16_4") (pintype "bidirectional+no_connect"))
    )
    (net (code "62") (name "unconnected-(U1-MISO-Pad10)") (class "Default")
      (node (ref "U1") (pin "10") (pinfunction "MISO_10") (pintype "bidirectional+no_connect"))
    )
    (net (code "63") (name "unconnected-(U1-MOSI-Pad13)") (class "Default")
      (node (ref "U1") (pin "13") (pinfunction "MOSI_13") (pintype "bidirectional+no_connect"))
    )
    (net (code "64") (name "unconnected-(U1-SCLK-Pad14)") (class "Default")
      (node (ref "U1") (pin "14") (pinfunction "SCLK_14") (pintype "input+no_connect"))
    )
    (net (code "65") (name "unconnected-(U2-PA15-Pad38)") (class "Default")
      (node (ref "U2") (pin "38") (pinfunction "PA15_38") (pintype "bidirectional+no_connect"))
    )
    (net (code "66") (name "unconnected-(U2-PB15-Pad28)") (class "Default")
      (node (ref "U2") (pin "28") (pinfunction "PB15_28") (pintype "bidirectional+no_connect"))
    )
    (net (code "67") (name "unconnected-(U2-PC13-TAMPER-RTC-Pad2)") (class "Default")
      (node (ref "U2") (pin "2") (pinfunction "PC13-TAMPER-RTC_2") (pintype "bidirectional+no_connect"))
    )
    (net (code "68") (name "unconnected-(U2-PC14-OSC32_IN-Pad3)") (class "Default")
      (node (ref "U2") (pin "3") (pinfunction "PC14-OSC32_IN_3") (pintype "bidirectional+no_connect"))
    )
    (net (code "69") (name "unconnected-(U2-PC15-OSC32_OUT-Pad4)") (class "Default")
      (node (ref "U2") (pin "4") (pinfunction "PC15-OSC32_OUT_4") (pintype "bidirectional+no_connect"))
    )
    (net (code "70") (name "unconnected-(U2-VBAT-Pad1)") (class "Default")
      (node (ref "U2") (pin "1") (pinfunction "VBAT_1") (pintype "bidirectional+no_connect"))
    )
    (net (code "71") (name "unconnected-(U3-NC-Pad4)") (class "Default")
      (node (ref "U3") (pin "4") (pinfunction "NC_4") (pintype "passive+no_connect"))
    )
  )
)
